# legacy-codec.net
KiCad netlist of a schematic drawn in Altium Designer
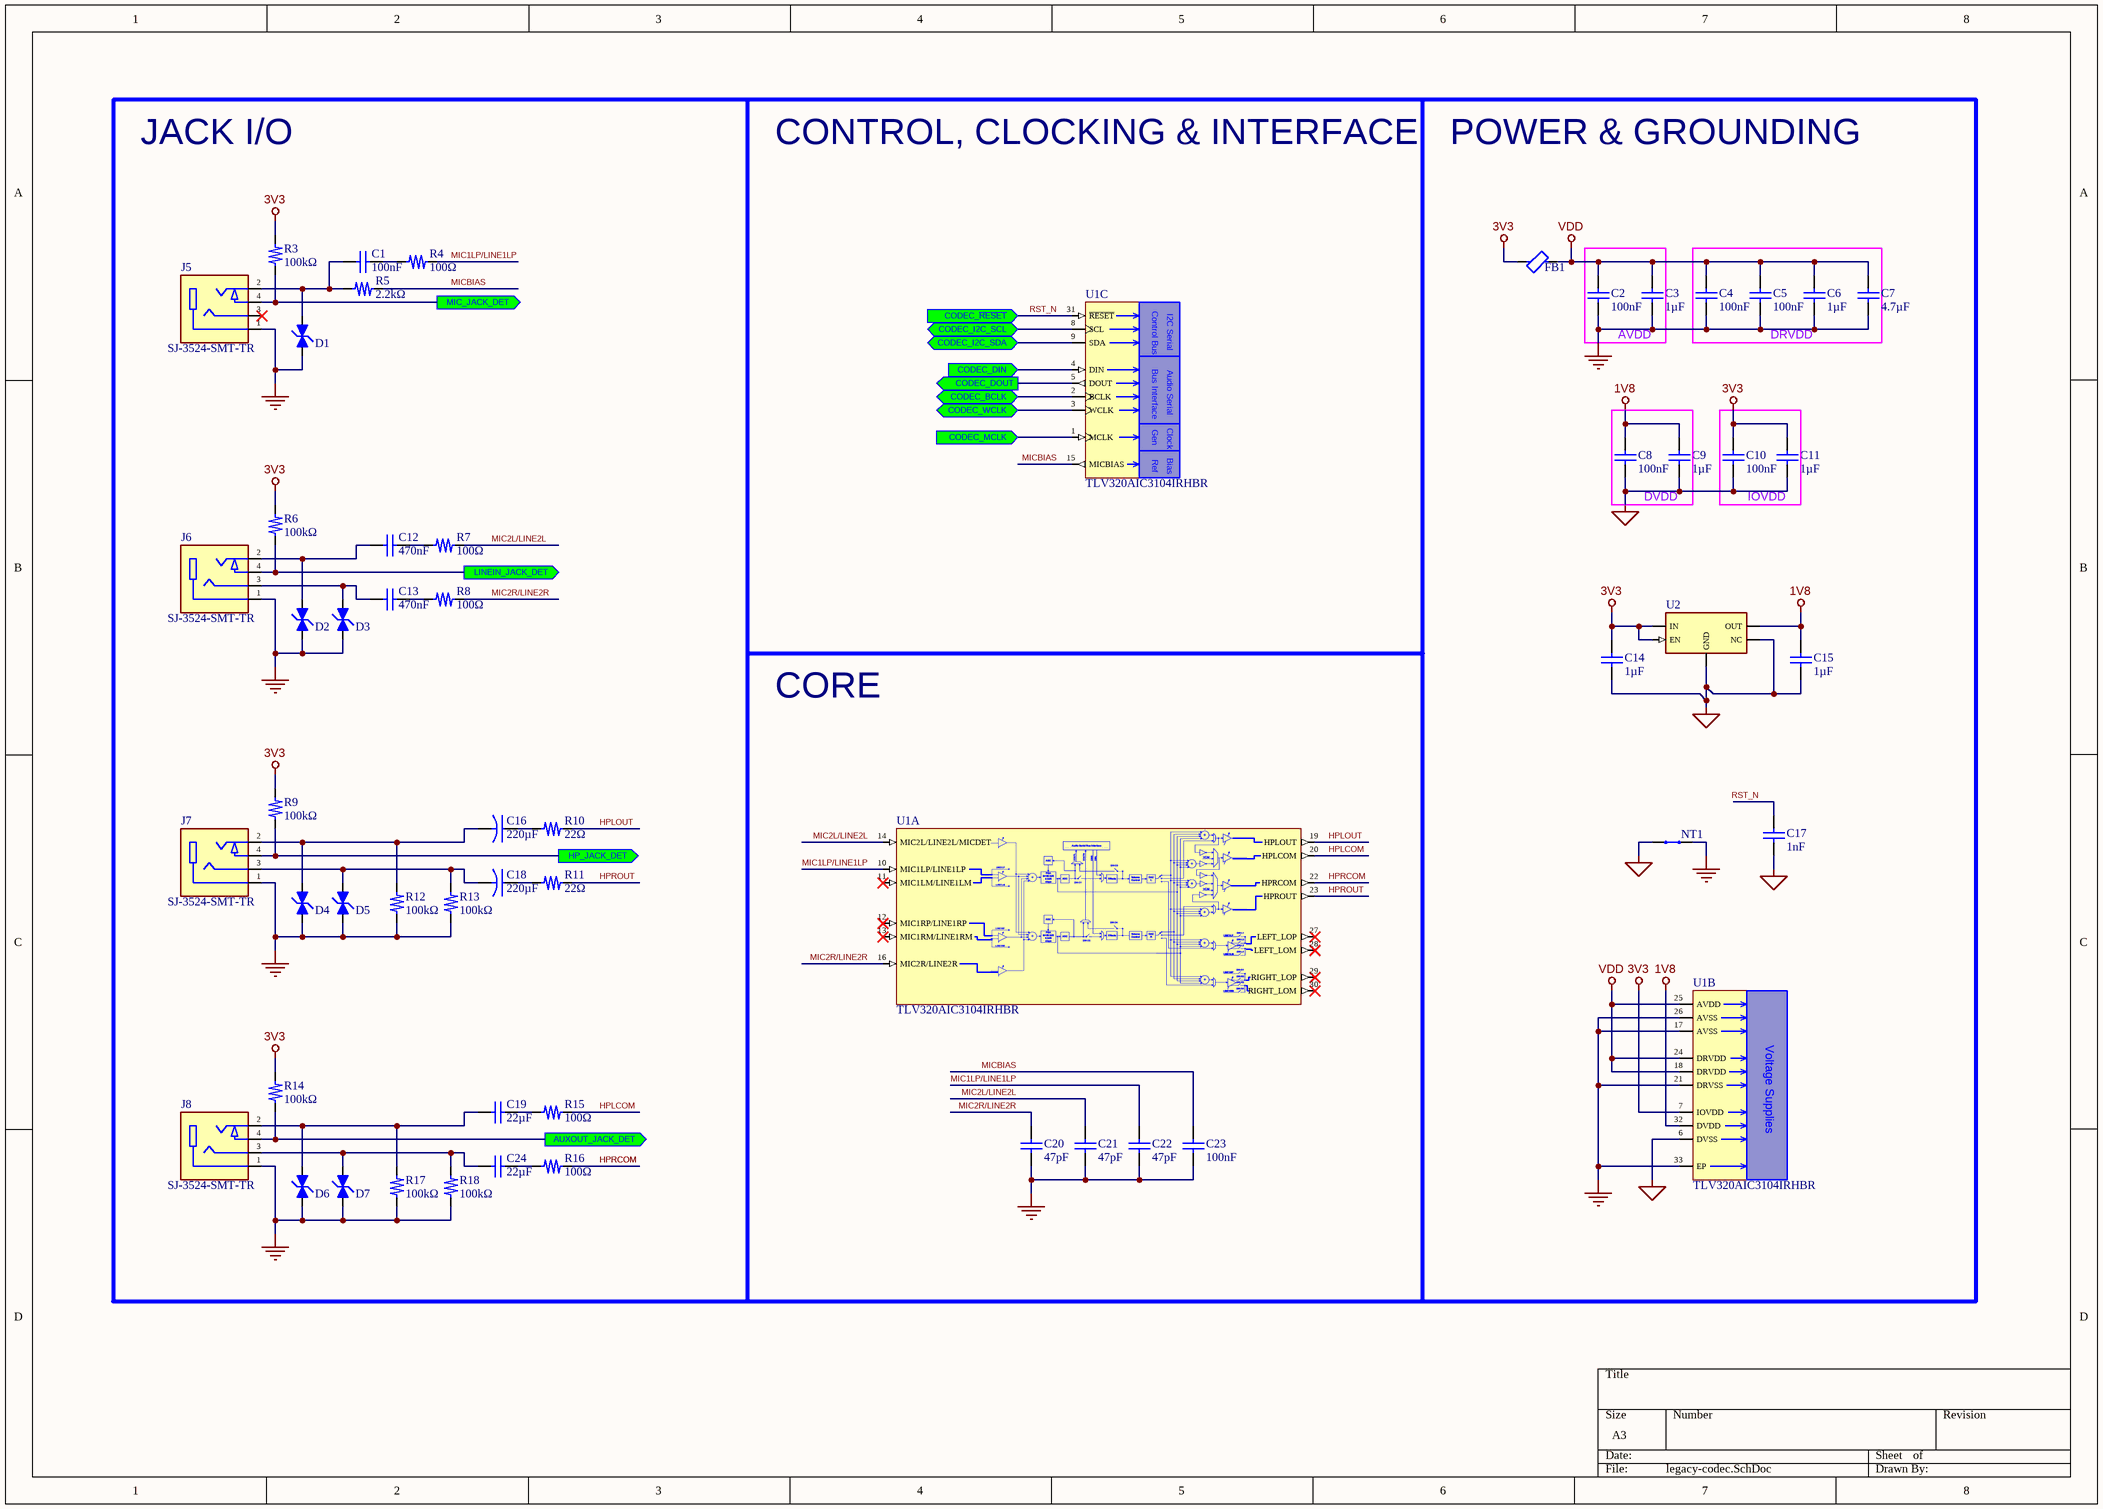
[diagram p0: legacy-codec.SchDoc]

(export (version "E")
  (design (tool "Eeschema 10.0.6"))
  (components
    (comp (ref "C1")
      (value "100nF")
      (footprint "CAPC2012X135N")
      (description "50V 100nF X7R ±10% 0805 Multilayer Ceramic Capacitors MLCC - SMD/SMT ROHS")
      (fields
        (field (name "MANUFACTURER") "YAGEO")
        (field (name "MANUFACTURER PART NUMBER") "CC0805KRX7R9BB104")
      )
      (libsource (lib "Capacitors") (part "CC0805KRX7R9BB104"))
    )
    (comp (ref "C2")
      (value "100nF")
      (footprint "CAPC2012X135N")
      (description "50V 100nF X7R ±10% 0805 Multilayer Ceramic Capacitors MLCC - SMD/SMT ROHS")
      (fields
        (field (name "MANUFACTURER") "YAGEO")
        (field (name "MANUFACTURER PART NUMBER") "CC0805KRX7R9BB104")
      )
      (libsource (lib "Capacitors") (part "CC0805KRX7R9BB104"))
    )
    (comp (ref "C3")
      (value "1µF")
      (footprint "CAPC2012X135N")
      (description "50V 1uF X7R ±10% 0805 Multilayer Ceramic Capacitors MLCC - SMD/SMT ROHS")
      (fields
        (field (name "MANUFACTURER") "Samsung Electro-Mechanics")
        (field (name "MANUFACTURER PART NUMBER") "CL21B105KBFNNNE")
      )
      (libsource (lib "Capacitors") (part "CL21B105KBFNNNE"))
    )
    (comp (ref "C4")
      (value "100nF")
      (footprint "CAPC2012X135N")
      (description "50V 100nF X7R ±10% 0805 Multilayer Ceramic Capacitors MLCC - SMD/SMT ROHS")
      (fields
        (field (name "MANUFACTURER") "YAGEO")
        (field (name "MANUFACTURER PART NUMBER") "CC0805KRX7R9BB104")
      )
      (libsource (lib "Capacitors") (part "CC0805KRX7R9BB104"))
    )
    (comp (ref "C5")
      (value "100nF")
      (footprint "CAPC2012X135N")
      (description "50V 100nF X7R ±10% 0805 Multilayer Ceramic Capacitors MLCC - SMD/SMT ROHS")
      (fields
        (field (name "MANUFACTURER") "YAGEO")
        (field (name "MANUFACTURER PART NUMBER") "CC0805KRX7R9BB104")
      )
      (libsource (lib "Capacitors") (part "CC0805KRX7R9BB104"))
    )
    (comp (ref "C6")
      (value "1µF")
      (footprint "CAPC2012X135N")
      (description "50V 1uF X7R ±10% 0805 Multilayer Ceramic Capacitors MLCC - SMD/SMT ROHS")
      (fields
        (field (name "MANUFACTURER") "Samsung Electro-Mechanics")
        (field (name "MANUFACTURER PART NUMBER") "CL21B105KBFNNNE")
      )
      (libsource (lib "Capacitors") (part "CL21B105KBFNNNE"))
    )
    (comp (ref "C7")
      (value "4.7µF")
      (footprint "CAPC2012X135N")
      (description "25V 4.7uF X5R ±10% 0805 Multilayer Ceramic Capacitors MLCC - SMD/SMT ROHS")
      (fields
        (field (name "MANUFACTURER") "YAGEO")
        (field (name "MANUFACTURER PART NUMBER") "CC0805KKX5R8BB475")
      )
      (libsource (lib "Capacitors") (part "CC0805KKX5R8BB475"))
    )
    (comp (ref "C8")
      (value "100nF")
      (footprint "CAPC2012X135N")
      (description "50V 100nF X7R ±10% 0805 Multilayer Ceramic Capacitors MLCC - SMD/SMT ROHS")
      (fields
        (field (name "MANUFACTURER") "YAGEO")
        (field (name "MANUFACTURER PART NUMBER") "CC0805KRX7R9BB104")
      )
      (libsource (lib "Capacitors") (part "CC0805KRX7R9BB104"))
    )
    (comp (ref "C9")
      (value "1µF")
      (footprint "CAPC2012X135N")
      (description "50V 1uF X7R ±10% 0805 Multilayer Ceramic Capacitors MLCC - SMD/SMT ROHS")
      (fields
        (field (name "MANUFACTURER") "Samsung Electro-Mechanics")
        (field (name "MANUFACTURER PART NUMBER") "CL21B105KBFNNNE")
      )
      (libsource (lib "Capacitors") (part "CL21B105KBFNNNE"))
    )
    (comp (ref "C10")
      (value "100nF")
      (footprint "CAPC2012X135N")
      (description "50V 100nF X7R ±10% 0805 Multilayer Ceramic Capacitors MLCC - SMD/SMT ROHS")
      (fields
        (field (name "MANUFACTURER") "YAGEO")
        (field (name "MANUFACTURER PART NUMBER") "CC0805KRX7R9BB104")
      )
      (libsource (lib "Capacitors") (part "CC0805KRX7R9BB104"))
    )
    (comp (ref "C11")
      (value "1µF")
      (footprint "CAPC2012X135N")
      (description "50V 1uF X7R ±10% 0805 Multilayer Ceramic Capacitors MLCC - SMD/SMT ROHS")
      (fields
        (field (name "MANUFACTURER") "Samsung Electro-Mechanics")
        (field (name "MANUFACTURER PART NUMBER") "CL21B105KBFNNNE")
      )
      (libsource (lib "Capacitors") (part "CL21B105KBFNNNE"))
    )
    (comp (ref "C12")
      (value "470nF")
      (footprint "CAPC2012X135N")
      (fields (field (name "MANUFACTURER") "KEMET") (field (name "Comment") "C0805C474K5RECTU"))
      (libsource (lib "Capacitors") (part "C0805C474K5RECTU"))
    )
    (comp (ref "C13")
      (value "470nF")
      (footprint "CAPC2012X135N")
      (fields (field (name "MANUFACTURER") "KEMET") (field (name "Comment") "C0805C474K5RECTU"))
      (libsource (lib "Capacitors") (part "C0805C474K5RECTU"))
    )
    (comp (ref "C14")
      (value "1µF")
      (footprint "CAPC2012X135N")
      (description "50V 1uF X7R ±10% 0805 Multilayer Ceramic Capacitors MLCC - SMD/SMT ROHS")
      (fields
        (field (name "MANUFACTURER") "Samsung Electro-Mechanics")
        (field (name "MANUFACTURER PART NUMBER") "CL21B105KBFNNNE")
      )
      (libsource (lib "Capacitors") (part "CL21B105KBFNNNE"))
    )
    (comp (ref "C15")
      (value "1µF")
      (footprint "CAPC2012X135N")
      (description "50V 1uF X7R ±10% 0805 Multilayer Ceramic Capacitors MLCC - SMD/SMT ROHS")
      (fields
        (field (name "MANUFACTURER") "Samsung Electro-Mechanics")
        (field (name "MANUFACTURER PART NUMBER") "CL21B105KBFNNNE")
      )
      (libsource (lib "Capacitors") (part "CL21B105KBFNNNE"))
    )
    (comp (ref "C16")
      (value "220µF")
      (footprint "CAPPRD500W60D800H1150")
      (description "Radial Can ALUMINUM ELECTROLYTIC CAPACITOR FR 25V 220muF ±20% 0.315Dia 8.00mm")
      (fields
        (field (name "MANUFACTURER") "Panasonic Electronic Components")
        (field (name "MANUFACTURER PART NUMBER") "EEU-FR1E221B")
      )
      (libsource (lib "Capacitors") (part "EEU-FR1E221B"))
    )
    (comp (ref "C17")
      (value "1nF")
      (footprint "CAPC2012X135N")
      (description "Multilayer Ceramic Capacitors MLCC - SMD/SMT 1kV 1000pF X7R 0805 10% AEC-Q200")
      (fields
        (field (name "MANUFACTURER") "KEMET")
        (field (name "MANUFACTURER PART NUMBER") "C0805C102KDRACAUTO")
      )
      (libsource (lib "Capacitors") (part "C0805C102KDRACAUTO"))
    )
    (comp (ref "C18")
      (value "220µF")
      (footprint "CAPPRD500W60D800H1150")
      (description "Radial Can ALUMINUM ELECTROLYTIC CAPACITOR FR 25V 220muF ±20% 0.315Dia 8.00mm")
      (fields
        (field (name "MANUFACTURER") "Panasonic Electronic Components")
        (field (name "MANUFACTURER PART NUMBER") "EEU-FR1E221B")
      )
      (libsource (lib "Capacitors") (part "EEU-FR1E221B"))
    )
    (comp (ref "C19")
      (value "22µF")
      (footprint "CAPC2012X135N")
      (description "0805 22 uF 10 V ±20% Tolerance X5R Multilayer Ceramic Chip Capacitor")
      (fields
        (field (name "MANUFACTURER") "Murata Electronics")
        (field (name "MANUFACTURER PART NUMBER") "GRM21BR61A226ME44L")
      )
      (libsource (lib "Capacitors") (part "GRM21BR61A226ME44L"))
    )
    (comp (ref "C20")
      (value "47pF")
      (footprint "CAPC2012X135N")
      (description "50V 47pF C0G ±5% 0805 Multilayer Ceramic Capacitors MLCC - SMD/SMT ROHS")
      (fields
        (field (name "MANUFACTURER") "Samsung Electro-Mechanics")
        (field (name "MANUFACTURER PART NUMBER") "CL21C470JBANNNC")
      )
      (libsource (lib "Capacitors") (part "CL21C470JBANNNC"))
    )
    (comp (ref "C21")
      (value "47pF")
      (footprint "CAPC2012X135N")
      (description "50V 47pF C0G ±5% 0805 Multilayer Ceramic Capacitors MLCC - SMD/SMT ROHS")
      (fields
        (field (name "MANUFACTURER") "Samsung Electro-Mechanics")
        (field (name "MANUFACTURER PART NUMBER") "CL21C470JBANNNC")
      )
      (libsource (lib "Capacitors") (part "CL21C470JBANNNC"))
    )
    (comp (ref "C22")
      (value "47pF")
      (footprint "CAPC2012X135N")
      (description "50V 47pF C0G ±5% 0805 Multilayer Ceramic Capacitors MLCC - SMD/SMT ROHS")
      (fields
        (field (name "MANUFACTURER") "Samsung Electro-Mechanics")
        (field (name "MANUFACTURER PART NUMBER") "CL21C470JBANNNC")
      )
      (libsource (lib "Capacitors") (part "CL21C470JBANNNC"))
    )
    (comp (ref "C23")
      (value "100nF")
      (footprint "CAPC2012X135N")
      (description "50V 100nF X7R ±10% 0805 Multilayer Ceramic Capacitors MLCC - SMD/SMT ROHS")
      (fields
        (field (name "MANUFACTURER") "YAGEO")
        (field (name "MANUFACTURER PART NUMBER") "CC0805KRX7R9BB104")
      )
      (libsource (lib "Capacitors") (part "CC0805KRX7R9BB104"))
    )
    (comp (ref "C24")
      (value "22µF")
      (footprint "CAPC2012X135N")
      (description "0805 22 uF 10 V ±20% Tolerance X5R Multilayer Ceramic Chip Capacitor")
      (fields
        (field (name "MANUFACTURER") "Murata Electronics")
        (field (name "MANUFACTURER PART NUMBER") "GRM21BR61A226ME44L")
      )
      (libsource (lib "Capacitors") (part "GRM21BR61A226ME44L"))
    )
    (comp (ref "D1")
      (value "0402ESDA-AEC1")
      (footprint "0402ESDAAEC1-MFR")
      (description "ESD Suppressor Diode TVS Bi-Dir 30V 35Vc 2-Pin Case 0402(1005Metric) T/R")
      (fields (field (name "MANUFACTURER") "Eaton"))
      (libsource (lib "Diodes") (part "0402ESDA-AEC1"))
    )
    (comp (ref "D2")
      (value "0402ESDA-AEC1")
      (footprint "0402ESDAAEC1-MFR")
      (description "ESD Suppressor Diode TVS Bi-Dir 30V 35Vc 2-Pin Case 0402(1005Metric) T/R")
      (fields (field (name "MANUFACTURER") "Eaton"))
      (libsource (lib "Diodes") (part "0402ESDA-AEC1"))
    )
    (comp (ref "D3")
      (value "0402ESDA-AEC1")
      (footprint "0402ESDAAEC1-MFR")
      (description "ESD Suppressor Diode TVS Bi-Dir 30V 35Vc 2-Pin Case 0402(1005Metric) T/R")
      (fields (field (name "MANUFACTURER") "Eaton"))
      (libsource (lib "Diodes") (part "0402ESDA-AEC1"))
    )
    (comp (ref "D4")
      (value "0402ESDA-AEC1")
      (footprint "0402ESDAAEC1-MFR")
      (description "ESD Suppressor Diode TVS Bi-Dir 30V 35Vc 2-Pin Case 0402(1005Metric) T/R")
      (fields (field (name "MANUFACTURER") "Eaton"))
      (libsource (lib "Diodes") (part "0402ESDA-AEC1"))
    )
    (comp (ref "D5")
      (value "0402ESDA-AEC1")
      (footprint "0402ESDAAEC1-MFR")
      (description "ESD Suppressor Diode TVS Bi-Dir 30V 35Vc 2-Pin Case 0402(1005Metric) T/R")
      (fields (field (name "MANUFACTURER") "Eaton"))
      (libsource (lib "Diodes") (part "0402ESDA-AEC1"))
    )
    (comp (ref "D6")
      (value "0402ESDA-AEC1")
      (footprint "0402ESDAAEC1-MFR")
      (description "ESD Suppressor Diode TVS Bi-Dir 30V 35Vc 2-Pin Case 0402(1005Metric) T/R")
      (fields (field (name "MANUFACTURER") "Eaton"))
      (libsource (lib "Diodes") (part "0402ESDA-AEC1"))
    )
    (comp (ref "D7")
      (value "0402ESDA-AEC1")
      (footprint "0402ESDAAEC1-MFR")
      (description "ESD Suppressor Diode TVS Bi-Dir 30V 35Vc 2-Pin Case 0402(1005Metric) T/R")
      (fields (field (name "MANUFACTURER") "Eaton"))
      (libsource (lib "Diodes") (part "0402ESDA-AEC1"))
    )
    (comp (ref "FB1")
      (value "BLM21PG221SN1D")
      (footprint "FP-BLM21-0_2-t0_85-e0_5-MFG")
      (description "220 Ohms @ 100 MHz 1 Power Line Ferrite Bead 0805 (2012 Metric) 2A 45mOhm")
      (libsource (lib "FerriteBeads") (part "BLM21PG221SN1D"))
    )
    (comp (ref "J5")
      (value "SJ-3524-SMT-TR")
      (footprint "AUDIOJACK_RA_SMT_3P5_TRS_1SW")
      (description "3.5 mm, Stereo, Right Angle, Surface Mount (SMT), Audio Jack Connector")
      (libsource (lib "Connectors") (part "SJ-3524-SMT-TR"))
    )
    (comp (ref "J6")
      (value "SJ-3524-SMT-TR")
      (footprint "AUDIOJACK_RA_SMT_3P5_TRS_1SW")
      (description "3.5 mm, Stereo, Right Angle, Surface Mount (SMT), Audio Jack Connector")
      (libsource (lib "Connectors") (part "SJ-3524-SMT-TR"))
    )
    (comp (ref "J7")
      (value "SJ-3524-SMT-TR")
      (footprint "AUDIOJACK_RA_SMT_3P5_TRS_1SW")
      (description "3.5 mm, Stereo, Right Angle, Surface Mount (SMT), Audio Jack Connector")
      (libsource (lib "Connectors") (part "SJ-3524-SMT-TR"))
    )
    (comp (ref "J8")
      (value "SJ-3524-SMT-TR")
      (footprint "AUDIOJACK_RA_SMT_3P5_TRS_1SW")
      (description "3.5 mm, Stereo, Right Angle, Surface Mount (SMT), Audio Jack Connector")
      (libsource (lib "Connectors") (part "SJ-3524-SMT-TR"))
    )
    (comp (ref "NT1")
      (value "NetTie_SMD")
      (footprint "NETTIE_SMD")
      (description "Net Tie SMD")
      (libsource (lib "NetTies") (part "NetTie_SMD"))
    )
    (comp (ref "R3")
      (value "100kΩ")
      (footprint "RESC2012")
      (description "125Mw Thick Film Resistors 100Ppm/ 1% 100K 0805 Chip Resistor Surface Mount Rohs")
      (fields
        (field (name "MANUFACTURER") "YAGEO")
        (field (name "MANUFACTURER PART NUMBER") "RC0805FR-07100KL")
      )
      (libsource (lib "Resistors") (part "RC0805FR-07100KL"))
    )
    (comp (ref "R4")
      (value "100Ω")
      (footprint "RESC2012")
      (description "125Mw Thick Film Resistors 100Ppm/ 1% 100 0805 Chip Resistor Surface Mount Rohs")
      (fields
        (field (name "MANUFACTURER") "YAGEO")
        (field (name "MANUFACTURER PART NUMBER") "RC0805FR-07100RL")
      )
      (libsource (lib "Resistors") (part "RC0805FR-07100RL"))
    )
    (comp (ref "R5")
      (value "2.2kΩ")
      (footprint "RESC2012")
      (description "125Mw Thick Film Resistors 100Ppm/ 1% 2.2K 0805 Chip Resistor Surface Mount Rohs")
      (fields
        (field (name "MANUFACTURER") "YAGEO")
        (field (name "MANUFACTURER PART NUMBER") "RC0805FR-072K2L")
      )
      (libsource (lib "Resistors") (part "RC0805FR-072K2L"))
    )
    (comp (ref "R6")
      (value "100kΩ")
      (footprint "RESC2012")
      (description "125Mw Thick Film Resistors 100Ppm/ 1% 100K 0805 Chip Resistor Surface Mount Rohs")
      (fields
        (field (name "MANUFACTURER") "YAGEO")
        (field (name "MANUFACTURER PART NUMBER") "RC0805FR-07100KL")
      )
      (libsource (lib "Resistors") (part "RC0805FR-07100KL"))
    )
    (comp (ref "R7")
      (value "100Ω")
      (footprint "RESC2012")
      (description "125Mw Thick Film Resistors 100Ppm/ 1% 100 0805 Chip Resistor Surface Mount Rohs")
      (fields
        (field (name "MANUFACTURER") "YAGEO")
        (field (name "MANUFACTURER PART NUMBER") "RC0805FR-07100RL")
      )
      (libsource (lib "Resistors") (part "RC0805FR-07100RL"))
    )
    (comp (ref "R8")
      (value "100Ω")
      (footprint "RESC2012")
      (description "125Mw Thick Film Resistors 100Ppm/ 1% 100 0805 Chip Resistor Surface Mount Rohs")
      (fields
        (field (name "MANUFACTURER") "YAGEO")
        (field (name "MANUFACTURER PART NUMBER") "RC0805FR-07100RL")
      )
      (libsource (lib "Resistors") (part "RC0805FR-07100RL"))
    )
    (comp (ref "R9")
      (value "100kΩ")
      (footprint "RESC2012")
      (description "125Mw Thick Film Resistors 100Ppm/ 1% 100K 0805 Chip Resistor Surface Mount Rohs")
      (fields
        (field (name "MANUFACTURER") "YAGEO")
        (field (name "MANUFACTURER PART NUMBER") "RC0805FR-07100KL")
      )
      (libsource (lib "Resistors") (part "RC0805FR-07100KL"))
    )
    (comp (ref "R10")
      (value "22Ω")
      (footprint "RESC2012")
      (description "Res Thick Film 0805 22 Ohm 5% 1/8W ±200ppm/°C Molded SMD SMD Paper Tape on Plastic Reel")
      (fields
        (field (name "MANUFACTURER") "Bourns Inc.")
        (field (name "MANUFACTURER PART NUMBER") "CR0805-JW-220ELF")
      )
      (libsource (lib "Resistors") (part "CR0805-JW-220ELF"))
    )
    (comp (ref "R11")
      (value "22Ω")
      (footprint "RESC2012")
      (description "Res Thick Film 0805 22 Ohm 5% 1/8W ±200ppm/°C Molded SMD SMD Paper Tape on Plastic Reel")
      (fields
        (field (name "MANUFACTURER") "Bourns Inc.")
        (field (name "MANUFACTURER PART NUMBER") "CR0805-JW-220ELF")
      )
      (libsource (lib "Resistors") (part "CR0805-JW-220ELF"))
    )
    (comp (ref "R12")
      (value "100kΩ")
      (footprint "RESC2012")
      (description "125Mw Thick Film Resistors 100Ppm/ 1% 100K 0805 Chip Resistor Surface Mount Rohs")
      (fields
        (field (name "MANUFACTURER") "YAGEO")
        (field (name "MANUFACTURER PART NUMBER") "RC0805FR-07100KL")
      )
      (libsource (lib "Resistors") (part "RC0805FR-07100KL"))
    )
    (comp (ref "R13")
      (value "100kΩ")
      (footprint "RESC2012")
      (description "125Mw Thick Film Resistors 100Ppm/ 1% 100K 0805 Chip Resistor Surface Mount Rohs")
      (fields
        (field (name "MANUFACTURER") "YAGEO")
        (field (name "MANUFACTURER PART NUMBER") "RC0805FR-07100KL")
      )
      (libsource (lib "Resistors") (part "RC0805FR-07100KL"))
    )
    (comp (ref "R14")
      (value "100kΩ")
      (footprint "RESC2012")
      (description "125Mw Thick Film Resistors 100Ppm/ 1% 100K 0805 Chip Resistor Surface Mount Rohs")
      (fields
        (field (name "MANUFACTURER") "YAGEO")
        (field (name "MANUFACTURER PART NUMBER") "RC0805FR-07100KL")
      )
      (libsource (lib "Resistors") (part "RC0805FR-07100KL"))
    )
    (comp (ref "R15")
      (value "100Ω")
      (footprint "RESC2012")
      (description "125Mw Thick Film Resistors 100Ppm/ 1% 100 0805 Chip Resistor Surface Mount Rohs")
      (fields
        (field (name "MANUFACTURER") "YAGEO")
        (field (name "MANUFACTURER PART NUMBER") "RC0805FR-07100RL")
      )
      (libsource (lib "Resistors") (part "RC0805FR-07100RL"))
    )
    (comp (ref "R16")
      (value "100Ω")
      (footprint "RESC2012")
      (description "125Mw Thick Film Resistors 100Ppm/ 1% 100 0805 Chip Resistor Surface Mount Rohs")
      (fields
        (field (name "MANUFACTURER") "YAGEO")
        (field (name "MANUFACTURER PART NUMBER") "RC0805FR-07100RL")
      )
      (libsource (lib "Resistors") (part "RC0805FR-07100RL"))
    )
    (comp (ref "R17")
      (value "100kΩ")
      (footprint "RESC2012")
      (description "125Mw Thick Film Resistors 100Ppm/ 1% 100K 0805 Chip Resistor Surface Mount Rohs")
      (fields
        (field (name "MANUFACTURER") "YAGEO")
        (field (name "MANUFACTURER PART NUMBER") "RC0805FR-07100KL")
      )
      (libsource (lib "Resistors") (part "RC0805FR-07100KL"))
    )
    (comp (ref "R18")
      (value "100kΩ")
      (footprint "RESC2012")
      (description "125Mw Thick Film Resistors 100Ppm/ 1% 100K 0805 Chip Resistor Surface Mount Rohs")
      (fields
        (field (name "MANUFACTURER") "YAGEO")
        (field (name "MANUFACTURER PART NUMBER") "RC0805FR-07100KL")
      )
      (libsource (lib "Resistors") (part "RC0805FR-07100KL"))
    )
    (comp (ref "U1")
      (value "TLV320AIC3104IRHBR")
      (footprint "QFN50P500X500X100_HS-33N")
      (description "Low-Power Stereo CODEC with 6 Inputs, 6 Outputs, HP Amp and Enhanced Digital Effects")
      (fields (field (name "MANUFACTURER") "Texas Instruments"))
      (libsource (lib "ICs") (part "TLV320AIC3104IRHBR"))
    )
    (comp (ref "U2")
      (value "TLV70018DDCR")
      (footprint "SOT95P280X110-5N")
      (description "200-mA, high-PSRR, low-IQ, low-dropout voltage regulator with enable 5-SOT-23-THIN -40 to 125")
      (libsource (lib "ICs") (part "TLV70018DDCR"))
    )
  )
  (nets
    (net (code "1") (name "/AUXOUT_JACK_DET") (class "Default")
      (node (ref "J8") (pin "4") (pinfunction "tip_switch_4") (pintype "passive"))
      (node (ref "R14") (pin "1") (pinfunction "1_1") (pintype "passive"))
    )
    (net (code "2") (name "/CODEC_BCLK") (class "Default")
      (node (ref "U1") (pin "2") (pinfunction "BCLK_2") (pintype "bidirectional"))
    )
    (net (code "3") (name "/CODEC_DIN") (class "Default")
      (node (ref "U1") (pin "4") (pinfunction "DIN_4") (pintype "input"))
    )
    (net (code "4") (name "/CODEC_DOUT") (class "Default")
      (node (ref "U1") (pin "5") (pinfunction "DOUT_5") (pintype "output"))
    )
    (net (code "5") (name "/CODEC_I2C_SCL") (class "Default")
      (node (ref "U1") (pin "8") (pinfunction "SCL_8") (pintype "bidirectional"))
    )
    (net (code "6") (name "/CODEC_I2C_SDA") (class "Default")
      (node (ref "U1") (pin "9") (pinfunction "SDA_9") (pintype "bidirectional"))
    )
    (net (code "7") (name "/CODEC_MCLK") (class "Default")
      (node (ref "U1") (pin "1") (pinfunction "MCLK_1") (pintype "input"))
    )
    (net (code "8") (name "/CODEC_WCLK") (class "Default")
      (node (ref "U1") (pin "3") (pinfunction "WCLK_3") (pintype "bidirectional"))
    )
    (net (code "9") (name "/HPLCOM") (class "Default")
      (node (ref "R15") (pin "1") (pinfunction "1_1") (pintype "passive"))
      (node (ref "U1") (pin "20") (pinfunction "HPLCOM_20") (pintype "output"))
    )
    (net (code "10") (name "/HPLOUT") (class "Default")
      (node (ref "R10") (pin "1") (pinfunction "1_1") (pintype "passive"))
      (node (ref "U1") (pin "19") (pinfunction "HPLOUT_19") (pintype "output"))
    )
    (net (code "11") (name "/HPRCOM") (class "Default")
      (node (ref "R16") (pin "1") (pinfunction "1_1") (pintype "passive"))
      (node (ref "U1") (pin "22") (pinfunction "HPRCOM_22") (pintype "output"))
    )
    (net (code "12") (name "/HPROUT") (class "Default")
      (node (ref "R11") (pin "1") (pinfunction "1_1") (pintype "passive"))
      (node (ref "U1") (pin "23") (pinfunction "HPROUT_23") (pintype "output"))
    )
    (net (code "13") (name "/HP_JACK_DET") (class "Default")
      (node (ref "J7") (pin "4") (pinfunction "tip_switch_4") (pintype "passive"))
      (node (ref "R9") (pin "1") (pinfunction "1_1") (pintype "passive"))
    )
    (net (code "14") (name "/LINEIN_JACK_DET") (class "Default")
      (node (ref "J6") (pin "4") (pinfunction "tip_switch_4") (pintype "passive"))
      (node (ref "R6") (pin "1") (pinfunction "1_1") (pintype "passive"))
    )
    (net (code "15") (name "/MIC1LP{slash}LINE1LP") (class "Default")
      (node (ref "C22") (pin "2") (pinfunction "2_2") (pintype "passive"))
      (node (ref "R4") (pin "2") (pinfunction "2_2") (pintype "passive"))
      (node (ref "U1") (pin "10") (pinfunction "MIC1LP/LINE1LP_10") (pintype "input"))
    )
    (net (code "16") (name "/MIC2L{slash}LINE2L") (class "Default")
      (node (ref "C21") (pin "2") (pinfunction "2_2") (pintype "passive"))
      (node (ref "R7") (pin "1") (pinfunction "1_1") (pintype "passive"))
      (node (ref "U1") (pin "14") (pinfunction "MIC2L/LINE2L/MICDET_14") (pintype "input"))
    )
    (net (code "17") (name "/MIC2R{slash}LINE2R") (class "Default")
      (node (ref "C20") (pin "2") (pinfunction "2_2") (pintype "passive"))
      (node (ref "R8") (pin "1") (pinfunction "1_1") (pintype "passive"))
      (node (ref "U1") (pin "16") (pinfunction "MIC2R/LINE2R_16") (pintype "input"))
    )
    (net (code "18") (name "/MICBIAS") (class "Default")
      (node (ref "C23") (pin "2") (pinfunction "2_2") (pintype "passive"))
      (node (ref "R5") (pin "1") (pinfunction "1_1") (pintype "passive"))
      (node (ref "U1") (pin "15") (pinfunction "MICBIAS_15") (pintype "output"))
    )
    (net (code "19") (name "/MIC_JACK_DET") (class "Default")
      (node (ref "J5") (pin "4") (pinfunction "tip_switch_4") (pintype "passive"))
      (node (ref "R3") (pin "1") (pinfunction "1_1") (pintype "passive"))
    )
    (net (code "20") (name "/RST_N") (class "Default")
      (node (ref "C17") (pin "2") (pinfunction "2_2") (pintype "passive"))
      (node (ref "U1") (pin "31") (pinfunction "~{RESET}_31") (pintype "input"))
    )
    (net (code "21") (name "1V8") (class "Default")
      (node (ref "C15") (pin "2") (pinfunction "2_2") (pintype "passive"))
      (node (ref "C8") (pin "2") (pinfunction "2_2") (pintype "passive"))
      (node (ref "C9") (pin "2") (pinfunction "2_2") (pintype "passive"))
      (node (ref "U1") (pin "32") (pinfunction "DVDD_32") (pintype "power_in"))
      (node (ref "U2") (pin "5") (pinfunction "OUT_5") (pintype "power_in"))
    )
    (net (code "22") (name "3V3") (class "Default")
      (node (ref "C10") (pin "2") (pinfunction "2_2") (pintype "passive"))
      (node (ref "C11") (pin "2") (pinfunction "2_2") (pintype "passive"))
      (node (ref "C14") (pin "2") (pinfunction "2_2") (pintype "passive"))
      (node (ref "FB1") (pin "2") (pinfunction "2_2") (pintype "passive"))
      (node (ref "R14") (pin "2") (pinfunction "2_2") (pintype "passive"))
      (node (ref "R3") (pin "2") (pinfunction "2_2") (pintype "passive"))
      (node (ref "R6") (pin "2") (pinfunction "2_2") (pintype "passive"))
      (node (ref "R9") (pin "2") (pinfunction "2_2") (pintype "passive"))
      (node (ref "U1") (pin "7") (pinfunction "IOVDD_7") (pintype "power_in"))
      (node (ref "U2") (pin "1") (pinfunction "IN_1") (pintype "power_in"))
      (node (ref "U2") (pin "3") (pinfunction "EN_3") (pintype "input"))
    )
    (net (code "23") (name "AGND") (class "Default")
      (node (ref "C2") (pin "1") (pinfunction "1_1") (pintype "passive"))
      (node (ref "C20") (pin "1") (pinfunction "1_1") (pintype "passive"))
      (node (ref "C21") (pin "1") (pinfunction "1_1") (pintype "passive"))
      (node (ref "C22") (pin "1") (pinfunction "1_1") (pintype "passive"))
      (node (ref "C23") (pin "1") (pinfunction "1_1") (pintype "passive"))
      (node (ref "C3") (pin "1") (pinfunction "1_1") (pintype "passive"))
      (node (ref "C4") (pin "1") (pinfunction "1_1") (pintype "passive"))
      (node (ref "C5") (pin "1") (pinfunction "1_1") (pintype "passive"))
      (node (ref "C6") (pin "1") (pinfunction "1_1") (pintype "passive"))
      (node (ref "C7") (pin "1") (pinfunction "1_1") (pintype "passive"))
      (node (ref "D1") (pin "1") (pinfunction "1_1") (pintype "passive"))
      (node (ref "D2") (pin "1") (pinfunction "1_1") (pintype "passive"))
      (node (ref "D3") (pin "1") (pinfunction "1_1") (pintype "passive"))
      (node (ref "D4") (pin "1") (pinfunction "1_1") (pintype "passive"))
      (node (ref "D5") (pin "1") (pinfunction "1_1") (pintype "passive"))
      (node (ref "D6") (pin "1") (pinfunction "1_1") (pintype "passive"))
      (node (ref "D7") (pin "1") (pinfunction "1_1") (pintype "passive"))
      (node (ref "J5") (pin "1") (pinfunction "sleeve_1") (pintype "passive"))
      (node (ref "J6") (pin "1") (pinfunction "sleeve_1") (pintype "passive"))
      (node (ref "J7") (pin "1") (pinfunction "sleeve_1") (pintype "passive"))
      (node (ref "J8") (pin "1") (pinfunction "sleeve_1") (pintype "passive"))
      (node (ref "NT1") (pin "2") (pinfunction "2_2") (pintype "passive"))
      (node (ref "R12") (pin "1") (pinfunction "1_1") (pintype "passive"))
      (node (ref "R13") (pin "1") (pinfunction "1_1") (pintype "passive"))
      (node (ref "R17") (pin "1") (pinfunction "1_1") (pintype "passive"))
      (node (ref "R18") (pin "1") (pinfunction "1_1") (pintype "passive"))
      (node (ref "U1") (pin "17") (pinfunction "AVSS_17") (pintype "power_in"))
      (node (ref "U1") (pin "21") (pinfunction "DRVSS_21") (pintype "power_in"))
      (node (ref "U1") (pin "26") (pinfunction "AVSS_26") (pintype "power_in"))
      (node (ref "U1") (pin "33") (pinfunction "EP_33") (pintype "power_in"))
    )
    (net (code "24") (name "DGND") (class "Default")
      (node (ref "C10") (pin "1") (pinfunction "1_1") (pintype "passive"))
      (node (ref "C11") (pin "1") (pinfunction "1_1") (pintype "passive"))
      (node (ref "C14") (pin "1") (pinfunction "1_1") (pintype "passive"))
      (node (ref "C15") (pin "1") (pinfunction "1_1") (pintype "passive"))
      (node (ref "C17") (pin "1") (pinfunction "1_1") (pintype "passive"))
      (node (ref "C8") (pin "1") (pinfunction "1_1") (pintype "passive"))
      (node (ref "C9") (pin "1") (pinfunction "1_1") (pintype "passive"))
      (node (ref "NT1") (pin "1") (pinfunction "1_1") (pintype "passive"))
      (node (ref "U1") (pin "6") (pinfunction "DVSS_6") (pintype "power_in"))
      (node (ref "U2") (pin "2") (pinfunction "GND_2") (pintype "power_in"))
      (node (ref "U2") (pin "4") (pinfunction "NC_4") (pintype "passive"))
    )
    (net (code "25") (name "Net-(C1-Pad1)") (class "Default")
      (node (ref "C1") (pin "1") (pinfunction "1_1") (pintype "passive"))
      (node (ref "R4") (pin "1") (pinfunction "1_1") (pintype "passive"))
    )
    (net (code "26") (name "Net-(C12-Pad1)") (class "Default")
      (node (ref "C12") (pin "1") (pinfunction "1_1") (pintype "passive"))
      (node (ref "R7") (pin "2") (pinfunction "2_2") (pintype "passive"))
    )
    (net (code "27") (name "Net-(C13-Pad1)") (class "Default")
      (node (ref "C13") (pin "1") (pinfunction "1_1") (pintype "passive"))
      (node (ref "R8") (pin "2") (pinfunction "2_2") (pintype "passive"))
    )
    (net (code "28") (name "Net-(C16-PadP)") (class "Default")
      (node (ref "C16") (pin "P") (pinfunction "P_P") (pintype "passive"))
      (node (ref "R10") (pin "2") (pinfunction "2_2") (pintype "passive"))
    )
    (net (code "29") (name "Net-(C18-PadP)") (class "Default")
      (node (ref "C18") (pin "P") (pinfunction "P_P") (pintype "passive"))
      (node (ref "R11") (pin "2") (pinfunction "2_2") (pintype "passive"))
    )
    (net (code "30") (name "Net-(C19-Pad2)") (class "Default")
      (node (ref "C19") (pin "2") (pinfunction "2_2") (pintype "passive"))
      (node (ref "R15") (pin "2") (pinfunction "2_2") (pintype "passive"))
    )
    (net (code "31") (name "Net-(C24-Pad2)") (class "Default")
      (node (ref "C24") (pin "2") (pinfunction "2_2") (pintype "passive"))
      (node (ref "R16") (pin "2") (pinfunction "2_2") (pintype "passive"))
    )
    (net (code "32") (name "Net-(J5-tip)") (class "Default")
      (node (ref "C1") (pin "2") (pinfunction "2_2") (pintype "passive"))
      (node (ref "D1") (pin "2") (pinfunction "2_2") (pintype "passive"))
      (node (ref "J5") (pin "2") (pinfunction "tip_2") (pintype "passive"))
      (node (ref "R5") (pin "2") (pinfunction "2_2") (pintype "passive"))
    )
    (net (code "33") (name "Net-(J6-ring)") (class "Default")
      (node (ref "C13") (pin "2") (pinfunction "2_2") (pintype "passive"))
      (node (ref "D3") (pin "2") (pinfunction "2_2") (pintype "passive"))
      (node (ref "J6") (pin "3") (pinfunction "ring_3") (pintype "passive"))
    )
    (net (code "34") (name "Net-(J6-tip)") (class "Default")
      (node (ref "C12") (pin "2") (pinfunction "2_2") (pintype "passive"))
      (node (ref "D2") (pin "2") (pinfunction "2_2") (pintype "passive"))
      (node (ref "J6") (pin "2") (pinfunction "tip_2") (pintype "passive"))
    )
    (net (code "35") (name "Net-(J7-ring)") (class "Default")
      (node (ref "C18") (pin "N") (pinfunction "N_N") (pintype "passive"))
      (node (ref "D5") (pin "2") (pinfunction "2_2") (pintype "passive"))
      (node (ref "J7") (pin "3") (pinfunction "ring_3") (pintype "passive"))
      (node (ref "R13") (pin "2") (pinfunction "2_2") (pintype "passive"))
    )
    (net (code "36") (name "Net-(J7-tip)") (class "Default")
      (node (ref "C16") (pin "N") (pinfunction "N_N") (pintype "passive"))
      (node (ref "D4") (pin "2") (pinfunction "2_2") (pintype "passive"))
      (node (ref "J7") (pin "2") (pinfunction "tip_2") (pintype "passive"))
      (node (ref "R12") (pin "2") (pinfunction "2_2") (pintype "passive"))
    )
    (net (code "37") (name "Net-(J8-ring)") (class "Default")
      (node (ref "C24") (pin "1") (pinfunction "1_1") (pintype "passive"))
      (node (ref "D7") (pin "2") (pinfunction "2_2") (pintype "passive"))
      (node (ref "J8") (pin "3") (pinfunction "ring_3") (pintype "passive"))
      (node (ref "R18") (pin "2") (pinfunction "2_2") (pintype "passive"))
    )
    (net (code "38") (name "Net-(J8-tip)") (class "Default")
      (node (ref "C19") (pin "1") (pinfunction "1_1") (pintype "passive"))
      (node (ref "D6") (pin "2") (pinfunction "2_2") (pintype "passive"))
      (node (ref "J8") (pin "2") (pinfunction "tip_2") (pintype "passive"))
      (node (ref "R17") (pin "2") (pinfunction "2_2") (pintype "passive"))
    )
    (net (code "39") (name "VDD") (class "Default")
      (node (ref "C2") (pin "2") (pinfunction "2_2") (pintype "passive"))
      (node (ref "C3") (pin "2") (pinfunction "2_2") (pintype "passive"))
      (node (ref "C4") (pin "2") (pinfunction "2_2") (pintype "passive"))
      (node (ref "C5") (pin "2") (pinfunction "2_2") (pintype "passive"))
      (node (ref "C6") (pin "2") (pinfunction "2_2") (pintype "passive"))
      (node (ref "C7") (pin "2") (pinfunction "2_2") (pintype "passive"))
      (node (ref "FB1") (pin "1") (pinfunction "1_1") (pintype "passive"))
      (node (ref "U1") (pin "18") (pinfunction "DRVDD_18") (pintype "power_in"))
      (node (ref "U1") (pin "24") (pinfunction "DRVDD_24") (pintype "power_in"))
      (node (ref "U1") (pin "25") (pinfunction "AVDD_25") (pintype "power_in"))
    )
    (net (code "40") (name "unconnected-(J5-ring-Pad3)") (class "Default")
      (node (ref "J5") (pin "3") (pinfunction "ring_3") (pintype "passive+no_connect"))
    )
    (net (code "41") (name "unconnected-(U1A-LEFT_LOM-Pad28)") (class "Default")
      (node (ref "U1") (pin "28") (pinfunction "LEFT_LOM_28") (pintype "output+no_connect"))
    )
    (net (code "42") (name "unconnected-(U1A-LEFT_LOP-Pad27)") (class "Default")
      (node (ref "U1") (pin "27") (pinfunction "LEFT_LOP_27") (pintype "output+no_connect"))
    )
    (net (code "43") (name "unconnected-(U1A-MIC1LM{slash}LINE1LM-Pad11)") (class "Default")
      (node (ref "U1") (pin "11") (pinfunction "MIC1LM/LINE1LM_11") (pintype "input+no_connect"))
    )
    (net (code "44") (name "unconnected-(U1A-MIC1RM{slash}LINE1RM-Pad13)") (class "Default")
      (node (ref "U1") (pin "13") (pinfunction "MIC1RM/LINE1RM_13") (pintype "input+no_connect"))
    )
    (net (code "45") (name "unconnected-(U1A-MIC1RP{slash}LINE1RP-Pad12)") (class "Default")
      (node (ref "U1") (pin "12") (pinfunction "MIC1RP/LINE1RP_12") (pintype "input+no_connect"))
    )
    (net (code "46") (name "unconnected-(U1A-RIGHT_LOM-Pad30)") (class "Default")
      (node (ref "U1") (pin "30") (pinfunction "RIGHT_LOM_30") (pintype "output+no_connect"))
    )
    (net (code "47") (name "unconnected-(U1A-RIGHT_LOP-Pad29)") (class "Default")
      (node (ref "U1") (pin "29") (pinfunction "RIGHT_LOP_29") (pintype "output+no_connect"))
    )
  )
)
